# Multiplexer_Breakout.net
KiCad netlist of a schematic drawn in EAGLE
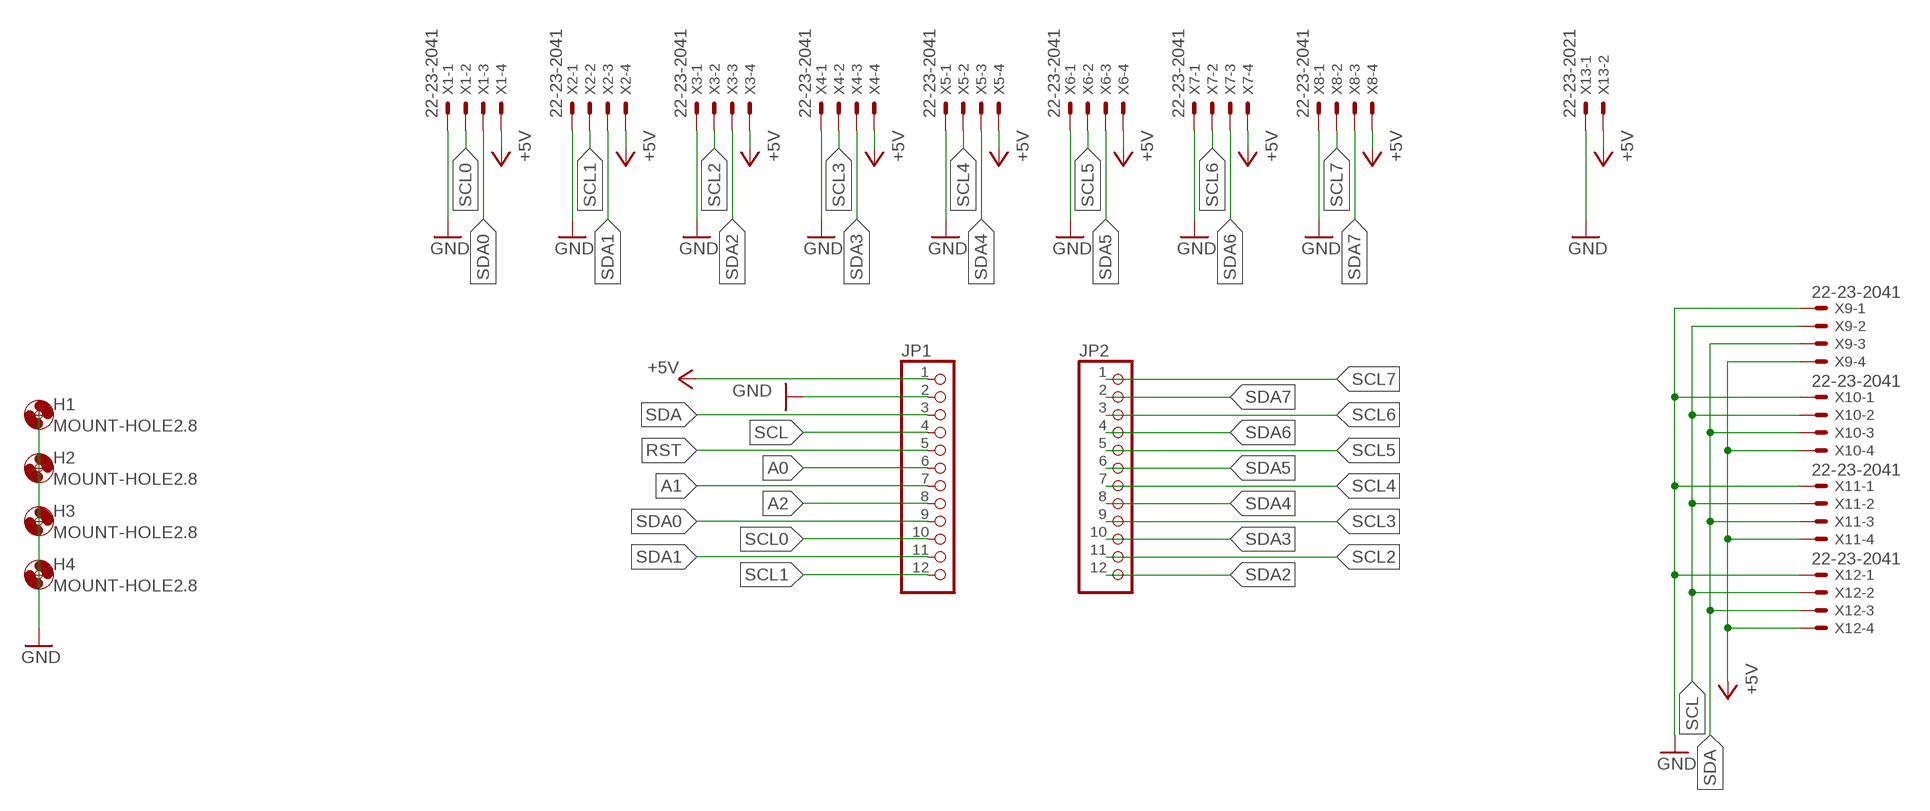
[diagram p0: schematic, sheet 1]

(export (version "E")
  (design (tool "Eeschema 10.0.6"))
  (components
    (comp (ref "H1")
      (value "MOUNT-HOLE2.8")
      (footprint "eagle-import:2,8")
      (libsource (lib "eagle-import") (part "MOUNT-HOLE2.8"))
    )
    (comp (ref "H2")
      (value "MOUNT-HOLE2.8")
      (footprint "eagle-import:2,8")
      (libsource (lib "eagle-import") (part "MOUNT-HOLE2.8"))
    )
    (comp (ref "H3")
      (value "MOUNT-HOLE2.8")
      (footprint "eagle-import:2,8")
      (libsource (lib "eagle-import") (part "MOUNT-HOLE2.8"))
    )
    (comp (ref "H4")
      (value "MOUNT-HOLE2.8")
      (footprint "eagle-import:2,8")
      (libsource (lib "eagle-import") (part "MOUNT-HOLE2.8"))
    )
    (comp (ref "JP1")
      (value "PINHD-1X12")
      (footprint "eagle-import:1X12")
      (libsource (lib "eagle-import") (part "PINHD-1X12"))
    )
    (comp (ref "JP2")
      (value "PINHD-1X12")
      (footprint "eagle-import:1X12")
      (libsource (lib "eagle-import") (part "PINHD-1X12"))
    )
    (comp (ref "X1")
      (value "22-23-2041")
      (footprint "eagle-import:22-23-2041")
      (fields (field (name "MF") "MOLEX"))
      (libsource (lib "eagle-import") (part "22-23-2041"))
    )
    (comp (ref "X2")
      (value "22-23-2041")
      (footprint "eagle-import:22-23-2041")
      (fields (field (name "MF") "MOLEX"))
      (libsource (lib "eagle-import") (part "22-23-2041"))
    )
    (comp (ref "X3")
      (value "22-23-2041")
      (footprint "eagle-import:22-23-2041")
      (fields (field (name "MF") "MOLEX"))
      (libsource (lib "eagle-import") (part "22-23-2041"))
    )
    (comp (ref "X4")
      (value "22-23-2041")
      (footprint "eagle-import:22-23-2041")
      (fields (field (name "MF") "MOLEX"))
      (libsource (lib "eagle-import") (part "22-23-2041"))
    )
    (comp (ref "X5")
      (value "22-23-2041")
      (footprint "eagle-import:22-23-2041")
      (fields (field (name "MF") "MOLEX"))
      (libsource (lib "eagle-import") (part "22-23-2041"))
    )
    (comp (ref "X6")
      (value "22-23-2041")
      (footprint "eagle-import:22-23-2041")
      (fields (field (name "MF") "MOLEX"))
      (libsource (lib "eagle-import") (part "22-23-2041"))
    )
    (comp (ref "X7")
      (value "22-23-2041")
      (footprint "eagle-import:22-23-2041")
      (fields (field (name "MF") "MOLEX"))
      (libsource (lib "eagle-import") (part "22-23-2041"))
    )
    (comp (ref "X8")
      (value "22-23-2041")
      (footprint "eagle-import:22-23-2041")
      (fields (field (name "MF") "MOLEX"))
      (libsource (lib "eagle-import") (part "22-23-2041"))
    )
    (comp (ref "X9")
      (value "22-23-2041")
      (footprint "eagle-import:22-23-2041")
      (fields (field (name "MF") "MOLEX"))
      (libsource (lib "eagle-import") (part "22-23-2041"))
    )
    (comp (ref "X10")
      (value "22-23-2041")
      (footprint "eagle-import:22-23-2041")
      (fields (field (name "MF") "MOLEX"))
      (libsource (lib "eagle-import") (part "22-23-2041"))
    )
    (comp (ref "X11")
      (value "22-23-2041")
      (footprint "eagle-import:22-23-2041")
      (fields (field (name "MF") "MOLEX"))
      (libsource (lib "eagle-import") (part "22-23-2041"))
    )
    (comp (ref "X12")
      (value "22-23-2041")
      (footprint "eagle-import:22-23-2041")
      (fields (field (name "MF") "MOLEX"))
      (libsource (lib "eagle-import") (part "22-23-2041"))
    )
    (comp (ref "X13")
      (value "22-23-2021")
      (footprint "eagle-import:22-23-2021")
      (fields (field (name "MF") "MOLEX"))
      (libsource (lib "eagle-import") (part "22-23-2021"))
    )
  )
  (nets
    (net (code "1") (name "+5V") (class "Default")
      (node (ref "JP1") (pin "1") (pinfunction "1_1") (pintype "passive"))
      (node (ref "X1") (pin "4") (pinfunction "S_4") (pintype "passive"))
      (node (ref "X10") (pin "4") (pinfunction "S_4") (pintype "passive"))
      (node (ref "X11") (pin "4") (pinfunction "S_4") (pintype "passive"))
      (node (ref "X12") (pin "4") (pinfunction "S_4") (pintype "passive"))
      (node (ref "X13") (pin "2") (pinfunction "S_2") (pintype "passive"))
      (node (ref "X2") (pin "4") (pinfunction "S_4") (pintype "passive"))
      (node (ref "X3") (pin "4") (pinfunction "S_4") (pintype "passive"))
      (node (ref "X4") (pin "4") (pinfunction "S_4") (pintype "passive"))
      (node (ref "X5") (pin "4") (pinfunction "S_4") (pintype "passive"))
      (node (ref "X6") (pin "4") (pinfunction "S_4") (pintype "passive"))
      (node (ref "X7") (pin "4") (pinfunction "S_4") (pintype "passive"))
      (node (ref "X8") (pin "4") (pinfunction "S_4") (pintype "passive"))
      (node (ref "X9") (pin "4") (pinfunction "S_4") (pintype "passive"))
    )
    (net (code "2") (name "A0") (class "Default")
      (node (ref "JP1") (pin "6") (pinfunction "6_6") (pintype "passive"))
    )
    (net (code "3") (name "A1") (class "Default")
      (node (ref "JP1") (pin "7") (pinfunction "7_7") (pintype "passive"))
    )
    (net (code "4") (name "A2") (class "Default")
      (node (ref "JP1") (pin "8") (pinfunction "8_8") (pintype "passive"))
    )
    (net (code "5") (name "GND") (class "Default")
      (node (ref "JP1") (pin "2") (pinfunction "2_2") (pintype "passive"))
      (node (ref "X1") (pin "1") (pinfunction "S_1") (pintype "passive"))
      (node (ref "X10") (pin "1") (pinfunction "S_1") (pintype "passive"))
      (node (ref "X11") (pin "1") (pinfunction "S_1") (pintype "passive"))
      (node (ref "X12") (pin "1") (pinfunction "S_1") (pintype "passive"))
      (node (ref "X13") (pin "1") (pinfunction "S_1") (pintype "passive"))
      (node (ref "X2") (pin "1") (pinfunction "S_1") (pintype "passive"))
      (node (ref "X3") (pin "1") (pinfunction "S_1") (pintype "passive"))
      (node (ref "X4") (pin "1") (pinfunction "S_1") (pintype "passive"))
      (node (ref "X5") (pin "1") (pinfunction "S_1") (pintype "passive"))
      (node (ref "X6") (pin "1") (pinfunction "S_1") (pintype "passive"))
      (node (ref "X7") (pin "1") (pinfunction "S_1") (pintype "passive"))
      (node (ref "X8") (pin "1") (pinfunction "S_1") (pintype "passive"))
      (node (ref "X9") (pin "1") (pinfunction "S_1") (pintype "passive"))
    )
    (net (code "6") (name "RST") (class "Default")
      (node (ref "JP1") (pin "5") (pinfunction "5_5") (pintype "passive"))
    )
    (net (code "7") (name "SCL") (class "Default")
      (node (ref "JP1") (pin "4") (pinfunction "4_4") (pintype "passive"))
      (node (ref "X10") (pin "2") (pinfunction "S_2") (pintype "passive"))
      (node (ref "X11") (pin "2") (pinfunction "S_2") (pintype "passive"))
      (node (ref "X12") (pin "2") (pinfunction "S_2") (pintype "passive"))
      (node (ref "X9") (pin "2") (pinfunction "S_2") (pintype "passive"))
    )
    (net (code "8") (name "SCL0") (class "Default")
      (node (ref "JP1") (pin "10") (pinfunction "10_10") (pintype "passive"))
      (node (ref "X1") (pin "2") (pinfunction "S_2") (pintype "passive"))
    )
    (net (code "9") (name "SCL1") (class "Default")
      (node (ref "JP1") (pin "12") (pinfunction "12_12") (pintype "passive"))
      (node (ref "X2") (pin "2") (pinfunction "S_2") (pintype "passive"))
    )
    (net (code "10") (name "SCL2") (class "Default")
      (node (ref "JP2") (pin "11") (pinfunction "11_11") (pintype "passive"))
      (node (ref "X3") (pin "2") (pinfunction "S_2") (pintype "passive"))
    )
    (net (code "11") (name "SCL3") (class "Default")
      (node (ref "JP2") (pin "9") (pinfunction "9_9") (pintype "passive"))
      (node (ref "X4") (pin "2") (pinfunction "S_2") (pintype "passive"))
    )
    (net (code "12") (name "SCL4") (class "Default")
      (node (ref "JP2") (pin "7") (pinfunction "7_7") (pintype "passive"))
      (node (ref "X5") (pin "2") (pinfunction "S_2") (pintype "passive"))
    )
    (net (code "13") (name "SCL5") (class "Default")
      (node (ref "JP2") (pin "5") (pinfunction "5_5") (pintype "passive"))
      (node (ref "X6") (pin "2") (pinfunction "S_2") (pintype "passive"))
    )
    (net (code "14") (name "SCL6") (class "Default")
      (node (ref "JP2") (pin "3") (pinfunction "3_3") (pintype "passive"))
      (node (ref "X7") (pin "2") (pinfunction "S_2") (pintype "passive"))
    )
    (net (code "15") (name "SCL7") (class "Default")
      (node (ref "JP2") (pin "1") (pinfunction "1_1") (pintype "passive"))
      (node (ref "X8") (pin "2") (pinfunction "S_2") (pintype "passive"))
    )
    (net (code "16") (name "SDA") (class "Default")
      (node (ref "JP1") (pin "3") (pinfunction "3_3") (pintype "passive"))
      (node (ref "X10") (pin "3") (pinfunction "S_3") (pintype "passive"))
      (node (ref "X11") (pin "3") (pinfunction "S_3") (pintype "passive"))
      (node (ref "X12") (pin "3") (pinfunction "S_3") (pintype "passive"))
      (node (ref "X9") (pin "3") (pinfunction "S_3") (pintype "passive"))
    )
    (net (code "17") (name "SDA0") (class "Default")
      (node (ref "JP1") (pin "9") (pinfunction "9_9") (pintype "passive"))
      (node (ref "X1") (pin "3") (pinfunction "S_3") (pintype "passive"))
    )
    (net (code "18") (name "SDA1") (class "Default")
      (node (ref "JP1") (pin "11") (pinfunction "11_11") (pintype "passive"))
      (node (ref "X2") (pin "3") (pinfunction "S_3") (pintype "passive"))
    )
    (net (code "19") (name "SDA2") (class "Default")
      (node (ref "JP2") (pin "12") (pinfunction "12_12") (pintype "passive"))
      (node (ref "X3") (pin "3") (pinfunction "S_3") (pintype "passive"))
    )
    (net (code "20") (name "SDA3") (class "Default")
      (node (ref "JP2") (pin "10") (pinfunction "10_10") (pintype "passive"))
      (node (ref "X4") (pin "3") (pinfunction "S_3") (pintype "passive"))
    )
    (net (code "21") (name "SDA4") (class "Default")
      (node (ref "JP2") (pin "8") (pinfunction "8_8") (pintype "passive"))
      (node (ref "X5") (pin "3") (pinfunction "S_3") (pintype "passive"))
    )
    (net (code "22") (name "SDA5") (class "Default")
      (node (ref "JP2") (pin "6") (pinfunction "6_6") (pintype "passive"))
      (node (ref "X6") (pin "3") (pinfunction "S_3") (pintype "passive"))
    )
    (net (code "23") (name "SDA6") (class "Default")
      (node (ref "JP2") (pin "4") (pinfunction "4_4") (pintype "passive"))
      (node (ref "X7") (pin "3") (pinfunction "S_3") (pintype "passive"))
    )
    (net (code "24") (name "SDA7") (class "Default")
      (node (ref "JP2") (pin "2") (pinfunction "2_2") (pintype "passive"))
      (node (ref "X8") (pin "3") (pinfunction "S_3") (pintype "passive"))
    )
  )
)
